# mcu_rev1.net
KiCad netlist of a schematic drawn in EAGLE
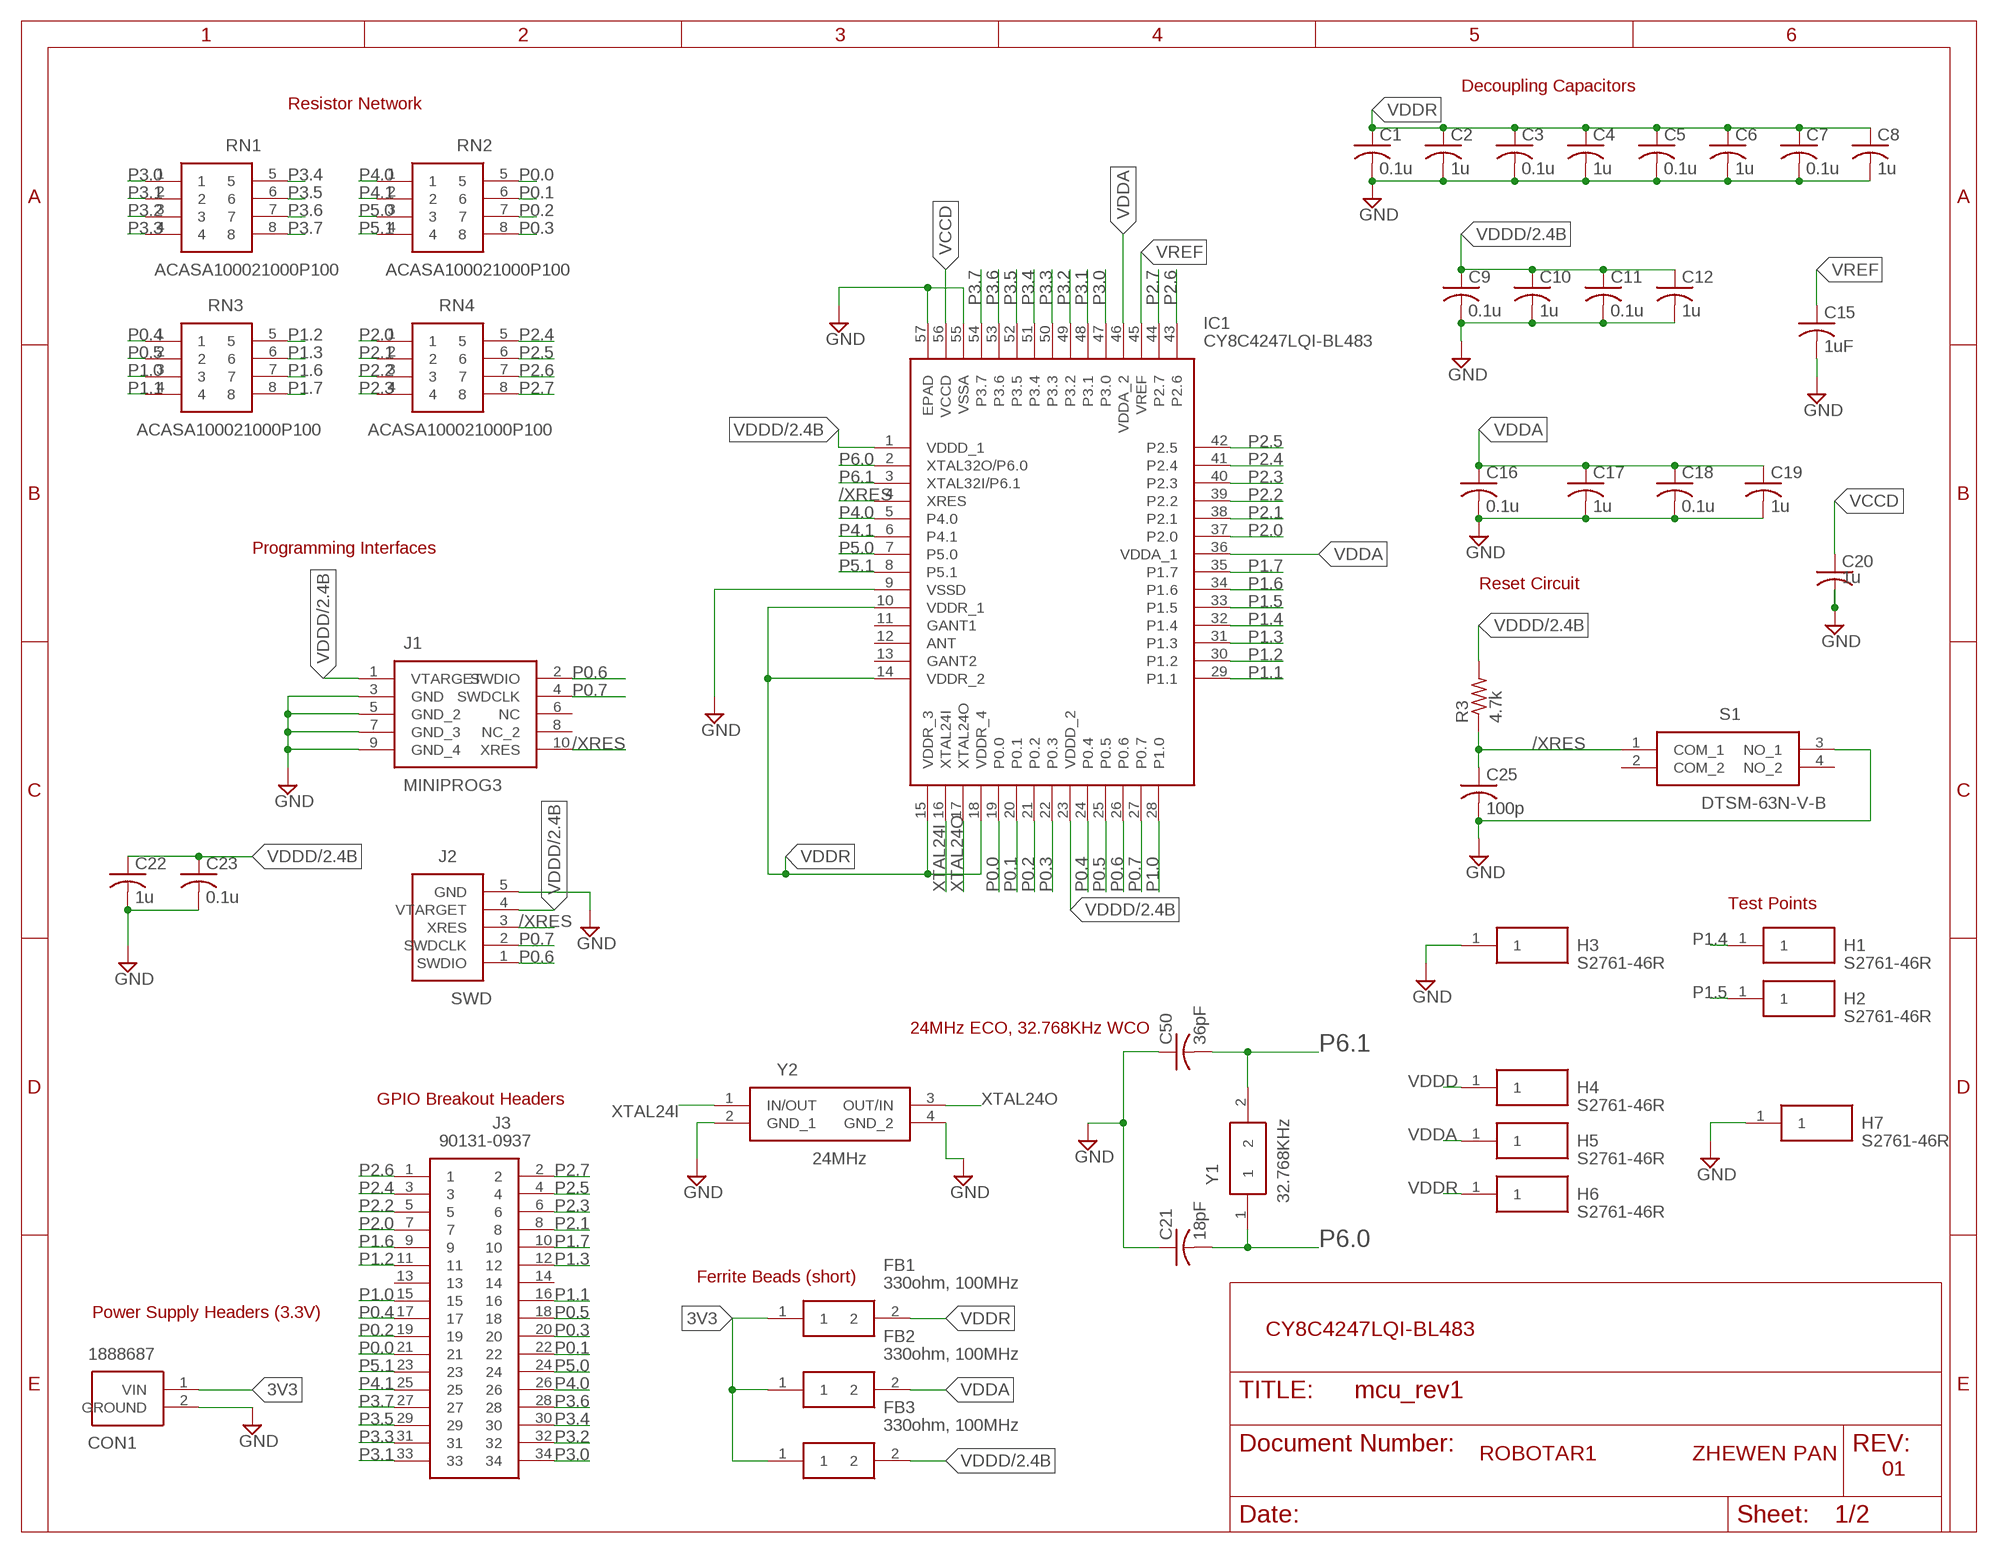
[diagram p0: schematic, sheet 1]
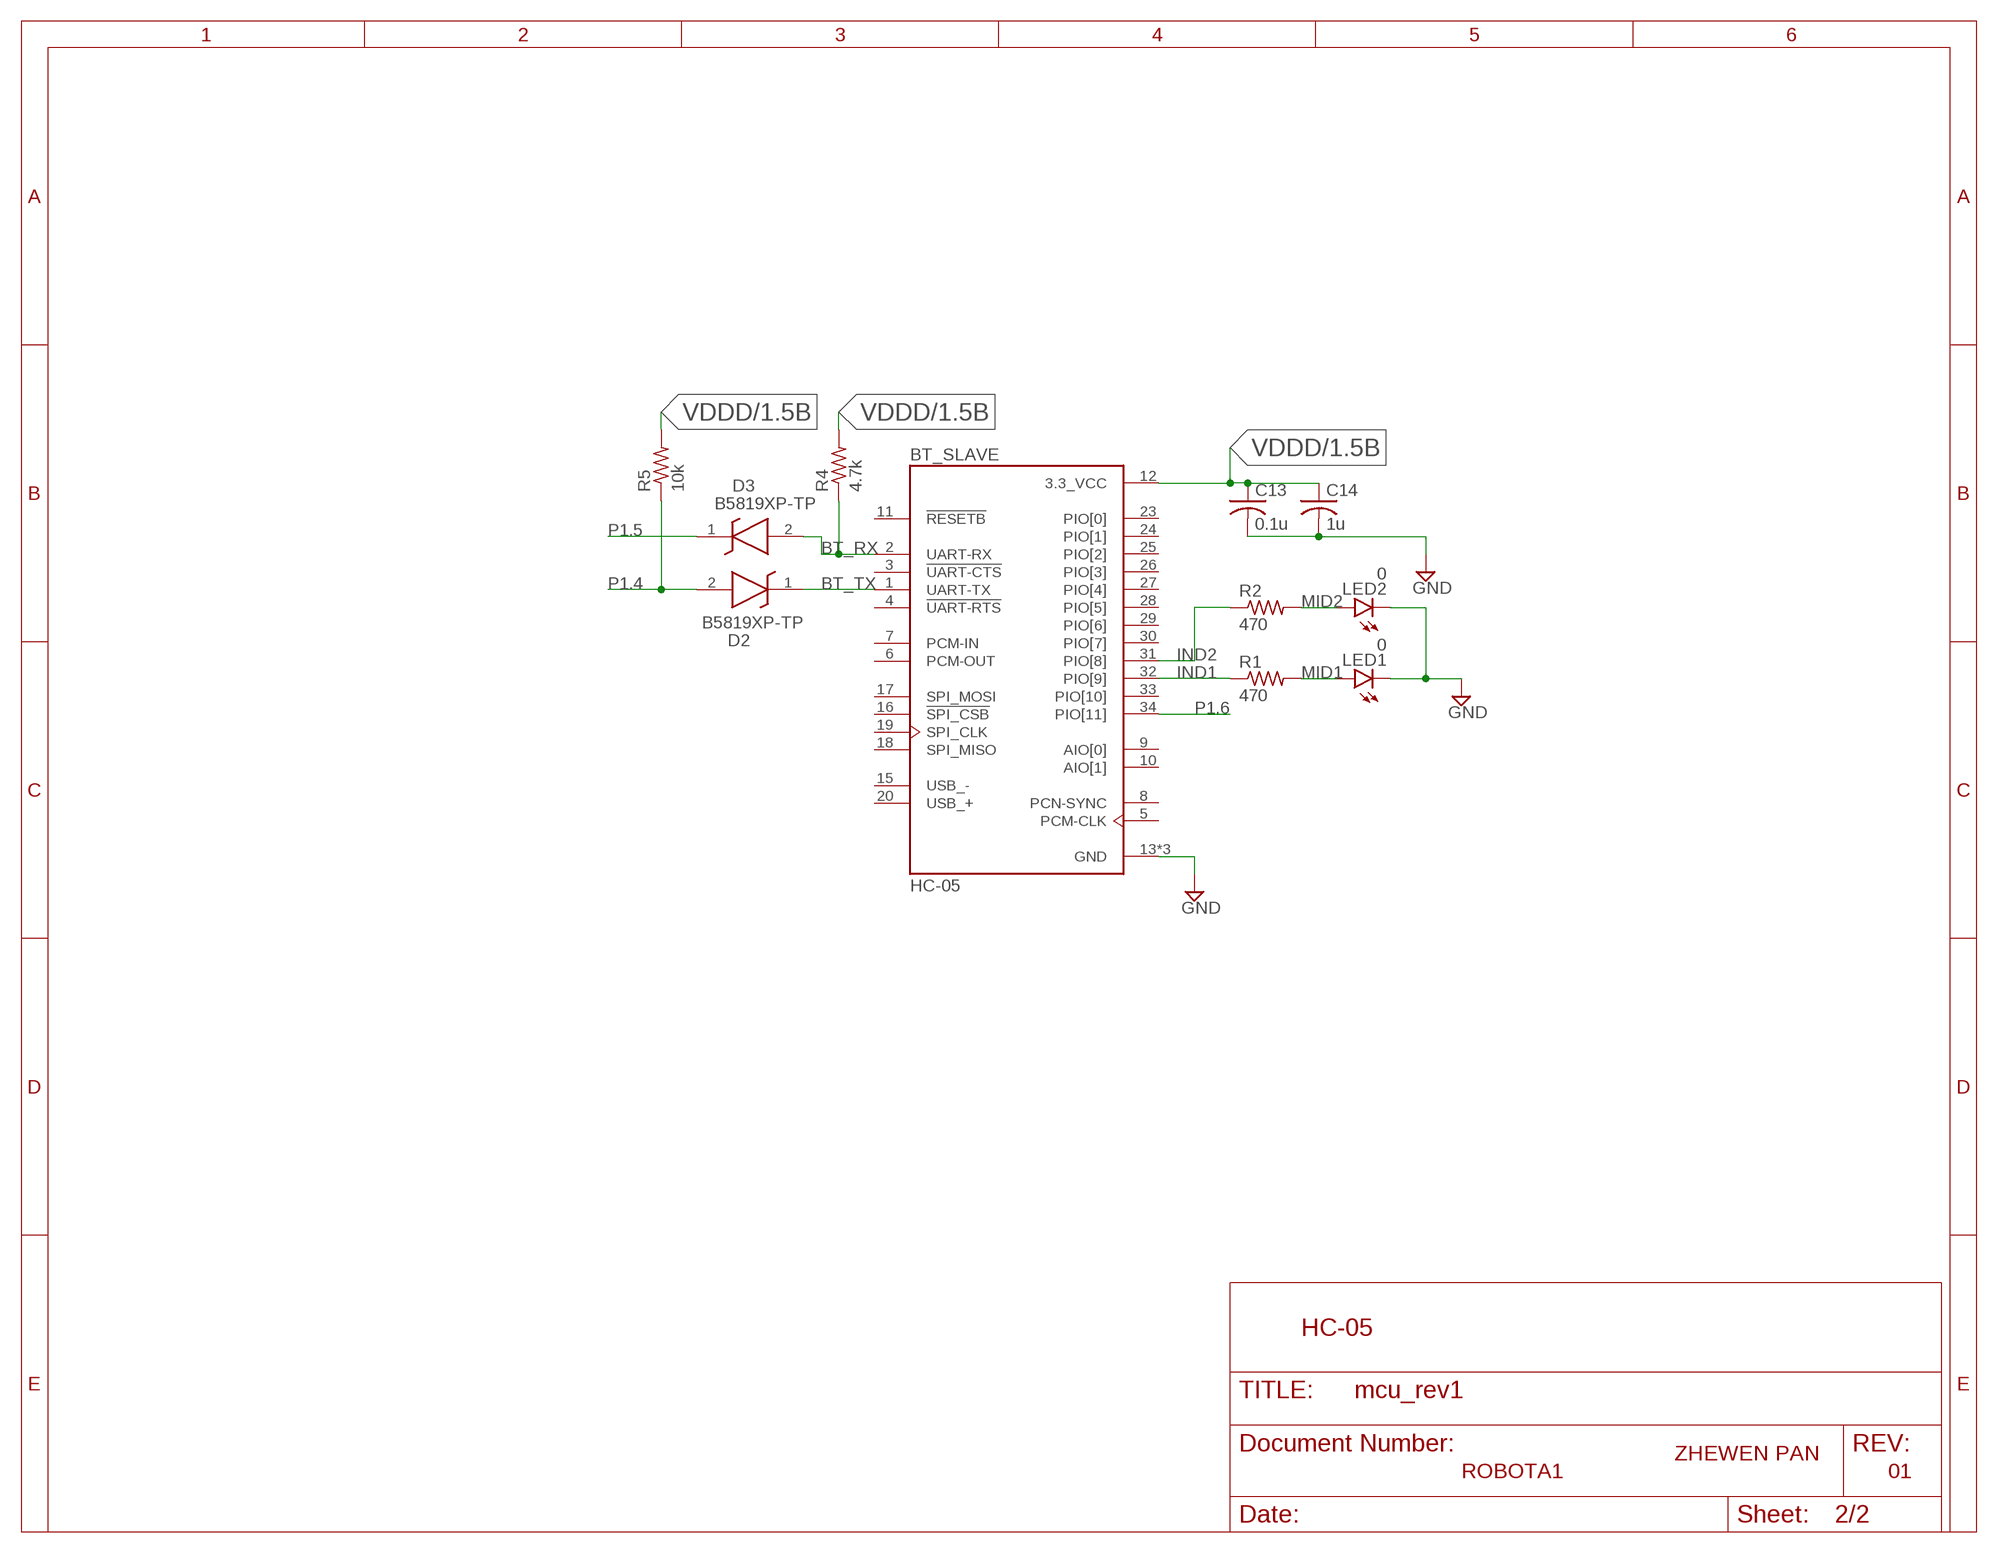
[diagram p1: schematic, sheet 2]

(export (version "E")
  (design (tool "Eeschema 10.0.6"))
  (components
    (comp (ref "BT_SLAVE")
      (value "HC-05")
      (footprint "eagle-import:XCVR_HC-05")
      (fields (field (name "MF") "Texas Instruments") (field (name "SPICEPREFIX") "X"))
      (libsource (lib "eagle-import") (part "HC-05"))
    )
    (comp (ref "C13")
      (value "0.1u")
      (footprint "eagle-import:C0805")
      (libsource (lib "eagle-import") (part "C-USC0805"))
    )
    (comp (ref "C14")
      (value "1u")
      (footprint "eagle-import:C0805")
      (libsource (lib "eagle-import") (part "C-USC0805"))
    )
    (comp (ref "D2")
      (value "B5819XP-TP")
      (footprint "eagle-import:B5819XPTP")
      (libsource (lib "eagle-import") (part "B5819XP-TP"))
    )
    (comp (ref "D3")
      (value "B5819XP-TP")
      (footprint "eagle-import:B5819XPTP")
      (libsource (lib "eagle-import") (part "B5819XP-TP"))
    )
    (comp (ref "LED1")
      (value "0")
      (footprint "eagle-import:SML0805")
      (libsource (lib "eagle-import") (part "LEDSML0805"))
    )
    (comp (ref "LED2")
      (value "0")
      (footprint "eagle-import:SML0805")
      (libsource (lib "eagle-import") (part "LEDSML0805"))
    )
    (comp (ref "R1")
      (value "470")
      (footprint "eagle-import:R0805")
      (libsource (lib "eagle-import") (part "R-US_R0805"))
    )
    (comp (ref "R2")
      (value "470")
      (footprint "eagle-import:R0805")
      (libsource (lib "eagle-import") (part "R-US_R0805"))
    )
    (comp (ref "R4")
      (value "4.7k")
      (footprint "eagle-import:R0805")
      (libsource (lib "eagle-import") (part "R-US_R0805"))
    )
    (comp (ref "R5")
      (value "10k")
      (footprint "eagle-import:R0805")
      (libsource (lib "eagle-import") (part "R-US_R0805"))
    )
    (comp (ref "C1")
      (value "0.1u")
      (footprint "eagle-import:C0805")
      (libsource (lib "eagle-import") (part "C-USC0805"))
    )
    (comp (ref "C2")
      (value "1u")
      (footprint "eagle-import:C0805")
      (libsource (lib "eagle-import") (part "C-USC0805"))
    )
    (comp (ref "C3")
      (value "0.1u")
      (footprint "eagle-import:C0805")
      (libsource (lib "eagle-import") (part "C-USC0805"))
    )
    (comp (ref "C4")
      (value "1u")
      (footprint "eagle-import:C0805")
      (libsource (lib "eagle-import") (part "C-USC0805"))
    )
    (comp (ref "C5")
      (value "0.1u")
      (footprint "eagle-import:C0805")
      (libsource (lib "eagle-import") (part "C-USC0805"))
    )
    (comp (ref "C6")
      (value "1u")
      (footprint "eagle-import:C0805")
      (libsource (lib "eagle-import") (part "C-USC0805"))
    )
    (comp (ref "C7")
      (value "0.1u")
      (footprint "eagle-import:C0805")
      (libsource (lib "eagle-import") (part "C-USC0805"))
    )
    (comp (ref "C8")
      (value "1u")
      (footprint "eagle-import:C0805")
      (libsource (lib "eagle-import") (part "C-USC0805"))
    )
    (comp (ref "C9")
      (value "0.1u")
      (footprint "eagle-import:C0805")
      (libsource (lib "eagle-import") (part "C-USC0805"))
    )
    (comp (ref "C10")
      (value "1u")
      (footprint "eagle-import:C0805")
      (libsource (lib "eagle-import") (part "C-USC0805"))
    )
    (comp (ref "C11")
      (value "0.1u")
      (footprint "eagle-import:C0805")
      (libsource (lib "eagle-import") (part "C-USC0805"))
    )
    (comp (ref "C12")
      (value "1u")
      (footprint "eagle-import:C0805")
      (libsource (lib "eagle-import") (part "C-USC0805"))
    )
    (comp (ref "C15")
      (value "1uF")
      (footprint "eagle-import:C0805")
      (libsource (lib "eagle-import") (part "C-USC0805"))
    )
    (comp (ref "C16")
      (value "0.1u")
      (footprint "eagle-import:C0805")
      (libsource (lib "eagle-import") (part "C-USC0805"))
    )
    (comp (ref "C17")
      (value "1u")
      (footprint "eagle-import:C0805")
      (libsource (lib "eagle-import") (part "C-USC0805"))
    )
    (comp (ref "C18")
      (value "0.1u")
      (footprint "eagle-import:C0805")
      (libsource (lib "eagle-import") (part "C-USC0805"))
    )
    (comp (ref "C19")
      (value "1u")
      (footprint "eagle-import:C0805")
      (libsource (lib "eagle-import") (part "C-USC0805"))
    )
    (comp (ref "C20")
      (value "1u")
      (footprint "eagle-import:C0805")
      (libsource (lib "eagle-import") (part "C-USC0805"))
    )
    (comp (ref "C21")
      (value "18pF")
      (footprint "eagle-import:C0805")
      (libsource (lib "eagle-import") (part "C-USC0805"))
    )
    (comp (ref "C22")
      (value "1u")
      (footprint "eagle-import:C0805")
      (libsource (lib "eagle-import") (part "C-USC0805"))
    )
    (comp (ref "C23")
      (value "0.1u")
      (footprint "eagle-import:C0805")
      (libsource (lib "eagle-import") (part "C-USC0805"))
    )
    (comp (ref "C25")
      (value "100p")
      (footprint "eagle-import:C0805")
      (libsource (lib "eagle-import") (part "C-USC0805"))
    )
    (comp (ref "C50")
      (value "36pF")
      (footprint "eagle-import:C0805")
      (libsource (lib "eagle-import") (part "C-USC0805"))
    )
    (comp (ref "CON1")
      (value "1888687")
      (footprint "eagle-import:SHDR2W90P0X508_1X2_1016X950X15")
      (fields (field (name "RS_PART_NUMBER") "8045095"))
      (libsource (lib "eagle-import") (part "1888687"))
    )
    (comp (ref "FB1")
      (value "330ohm, 100MHz")
      (footprint "eagle-import:BEADC2012X105N")
      (fields
        (field (name "MANUFACTURER_PART_NUMBER") "BLM21PG331SN1D")
        (field (name "RS_PART_NUMBER") "7241545P")
      )
      (libsource (lib "eagle-import") (part "BLM21PG331SN1D"))
    )
    (comp (ref "FB2")
      (value "330ohm, 100MHz")
      (footprint "eagle-import:BEADC2012X105N")
      (fields
        (field (name "MANUFACTURER_PART_NUMBER") "BLM21PG331SN1D")
        (field (name "RS_PART_NUMBER") "7241545P")
      )
      (libsource (lib "eagle-import") (part "BLM21PG331SN1D"))
    )
    (comp (ref "FB3")
      (value "330ohm, 100MHz")
      (footprint "eagle-import:BEADC2012X105N")
      (fields
        (field (name "MANUFACTURER_PART_NUMBER") "BLM21PG331SN1D")
        (field (name "RS_PART_NUMBER") "7241545P")
      )
      (libsource (lib "eagle-import") (part "BLM21PG331SN1D"))
    )
    (comp (ref "H1")
      (value "S2761-46R")
      (footprint "eagle-import:S276146R")
      (libsource (lib "eagle-import") (part "S2761-46R"))
    )
    (comp (ref "H2")
      (value "S2761-46R")
      (footprint "eagle-import:S276146R")
      (libsource (lib "eagle-import") (part "S2761-46R"))
    )
    (comp (ref "H3")
      (value "S2761-46R")
      (footprint "eagle-import:S276146R")
      (libsource (lib "eagle-import") (part "S2761-46R"))
    )
    (comp (ref "H4")
      (value "S2761-46R")
      (footprint "eagle-import:S276146R")
      (libsource (lib "eagle-import") (part "S2761-46R"))
    )
    (comp (ref "H5")
      (value "S2761-46R")
      (footprint "eagle-import:S276146R")
      (libsource (lib "eagle-import") (part "S2761-46R"))
    )
    (comp (ref "H6")
      (value "S2761-46R")
      (footprint "eagle-import:S276146R")
      (libsource (lib "eagle-import") (part "S2761-46R"))
    )
    (comp (ref "H7")
      (value "S2761-46R")
      (footprint "eagle-import:S276146R")
      (libsource (lib "eagle-import") (part "S2761-46R"))
    )
    (comp (ref "IC1")
      (value "CY8C4247LQI-BL483")
      (footprint "eagle-import:QFN40P700X700X60-57N")
      (fields (field (name "RS_PART_NUMBER") "1242964P"))
      (libsource (lib "eagle-import") (part "CY8C4247LQI-BL483"))
    )
    (comp (ref "J1")
      (value "MINIPROG3")
      (footprint "eagle-import:FTSH-105-01-L-DV-K")
      (fields
        (field (name "MANUFACTURER_PART_NUMBER") "FTSH-105-01-L-DV-K")
        (field (name "RS_PART_NUMBER") "1592332")
      )
      (libsource (lib "eagle-import") (part "FTSH-105-01-L-DV-K"))
    )
    (comp (ref "J2")
      (value "SWD")
      (footprint "eagle-import:HDRV5W64P0X254_1X5_1255X635X81")
      (fields
        (field (name "MANUFACTURER_PART_NUMBER") "22-23-2051")
        (field (name "RS_PART_NUMBER") "1888757")
      )
      (libsource (lib "eagle-import") (part "22-23-2051"))
    )
    (comp (ref "J3")
      (value "90131-0937")
      (footprint "eagle-import:HDRV34W90P254_2X17_4308X500X56")
      (fields (field (name "RS_PART_NUMBER") "6703569"))
      (libsource (lib "eagle-import") (part "90131-0937"))
    )
    (comp (ref "R3")
      (value "4.7k")
      (footprint "eagle-import:R0805")
      (libsource (lib "eagle-import") (part "R-US_R0805"))
    )
    (comp (ref "RN1")
      (value "ACASA100021000P100")
      (footprint "eagle-import:ACASA100021000P100")
      (fields (field (name "RS_PART_NUMBER") "6845742P"))
      (libsource (lib "eagle-import") (part "ACASA100021000P100"))
    )
    (comp (ref "RN2")
      (value "ACASA100021000P100")
      (footprint "eagle-import:ACASA100021000P100")
      (fields (field (name "RS_PART_NUMBER") "6845742P"))
      (libsource (lib "eagle-import") (part "ACASA100021000P100"))
    )
    (comp (ref "RN3")
      (value "ACASA100021000P100")
      (footprint "eagle-import:ACASA100021000P100")
      (fields (field (name "RS_PART_NUMBER") "6845742P"))
      (libsource (lib "eagle-import") (part "ACASA100021000P100"))
    )
    (comp (ref "RN4")
      (value "ACASA100021000P100")
      (footprint "eagle-import:ACASA100021000P100")
      (fields (field (name "RS_PART_NUMBER") "6845742P"))
      (libsource (lib "eagle-import") (part "ACASA100021000P100"))
    )
    (comp (ref "S1")
      (value "DTSM-63N-V-B")
      (footprint "eagle-import:DTSM63NVB")
      (libsource (lib "eagle-import") (part "DTSM-63N-V-B"))
    )
    (comp (ref "Y1")
      (value "32.768KHz")
      (footprint "eagle-import:ECX-31B")
      (fields (field (name "MANUFACTURER_PART_NUMBER") "ECS-.327-12.5-34B-TR"))
      (libsource (lib "eagle-import") (part "ECS-.327-12.5-34B-TR"))
    )
    (comp (ref "Y2")
      (value "24MHz")
      (footprint "eagle-import:ECS240836QAESTR")
      (fields (field (name "MANUFACTURER_PART_NUMBER") "ECS-240-8-36CKM-TR") (field (name "SPICEPREFIX") "E"))
      (libsource (lib "eagle-import") (part "ECS-240-8-36CKM-TR"))
    )
  )
  (nets
    (net (code "1") (name "3V3") (class "Default")
      (node (ref "CON1") (pin "1") (pinfunction "VIN_1") (pintype "bidirectional"))
      (node (ref "FB1") (pin "1") (pinfunction "1_1") (pintype "bidirectional"))
      (node (ref "FB2") (pin "1") (pinfunction "1_1") (pintype "bidirectional"))
      (node (ref "FB3") (pin "1") (pinfunction "1_1") (pintype "bidirectional"))
    )
    (net (code "2") (name "BT_RX") (class "Default")
      (node (ref "BT_SLAVE") (pin "2") (pinfunction "UART-RX_2") (pintype "input"))
      (node (ref "D3") (pin "2") (pinfunction "+_2") (pintype "bidirectional"))
      (node (ref "R4") (pin "1") (pinfunction "1_1") (pintype "passive"))
    )
    (net (code "3") (name "BT_TX") (class "Default")
      (node (ref "BT_SLAVE") (pin "1") (pinfunction "UART-TX_1") (pintype "output"))
      (node (ref "D2") (pin "1") (pinfunction "-_1") (pintype "bidirectional"))
    )
    (net (code "4") (name "GND") (class "Default")
      (node (ref "BT_SLAVE") (pin "13") (pinfunction "GND_13") (pintype "power_in"))
      (node (ref "BT_SLAVE") (pin "21") (pinfunction "GND_21") (pintype "power_in"))
      (node (ref "BT_SLAVE") (pin "22") (pinfunction "GND_22") (pintype "power_in"))
      (node (ref "C1") (pin "2") (pinfunction "2_2") (pintype "passive"))
      (node (ref "C10") (pin "2") (pinfunction "2_2") (pintype "passive"))
      (node (ref "C11") (pin "2") (pinfunction "2_2") (pintype "passive"))
      (node (ref "C12") (pin "2") (pinfunction "2_2") (pintype "passive"))
      (node (ref "C13") (pin "2") (pinfunction "2_2") (pintype "passive"))
      (node (ref "C14") (pin "2") (pinfunction "2_2") (pintype "passive"))
      (node (ref "C15") (pin "2") (pinfunction "2_2") (pintype "passive"))
      (node (ref "C16") (pin "2") (pinfunction "2_2") (pintype "passive"))
      (node (ref "C17") (pin "2") (pinfunction "2_2") (pintype "passive"))
      (node (ref "C18") (pin "2") (pinfunction "2_2") (pintype "passive"))
      (node (ref "C19") (pin "2") (pinfunction "2_2") (pintype "passive"))
      (node (ref "C2") (pin "2") (pinfunction "2_2") (pintype "passive"))
      (node (ref "C20") (pin "2") (pinfunction "2_2") (pintype "passive"))
      (node (ref "C21") (pin "1") (pinfunction "1_1") (pintype "passive"))
      (node (ref "C22") (pin "2") (pinfunction "2_2") (pintype "passive"))
      (node (ref "C23") (pin "2") (pinfunction "2_2") (pintype "passive"))
      (node (ref "C25") (pin "2") (pinfunction "2_2") (pintype "passive"))
      (node (ref "C3") (pin "2") (pinfunction "2_2") (pintype "passive"))
      (node (ref "C4") (pin "2") (pinfunction "2_2") (pintype "passive"))
      (node (ref "C5") (pin "2") (pinfunction "2_2") (pintype "passive"))
      (node (ref "C50") (pin "1") (pinfunction "1_1") (pintype "passive"))
      (node (ref "C6") (pin "2") (pinfunction "2_2") (pintype "passive"))
      (node (ref "C7") (pin "2") (pinfunction "2_2") (pintype "passive"))
      (node (ref "C8") (pin "2") (pinfunction "2_2") (pintype "passive"))
      (node (ref "C9") (pin "2") (pinfunction "2_2") (pintype "passive"))
      (node (ref "CON1") (pin "2") (pinfunction "GROUND_2") (pintype "bidirectional"))
      (node (ref "H3") (pin "1") (pinfunction "1_1") (pintype "bidirectional"))
      (node (ref "H7") (pin "1") (pinfunction "1_1") (pintype "bidirectional"))
      (node (ref "IC1") (pin "55") (pinfunction "VSSA_55") (pintype "bidirectional"))
      (node (ref "IC1") (pin "57") (pinfunction "EPAD_57") (pintype "bidirectional"))
      (node (ref "IC1") (pin "9") (pinfunction "VSSD_9") (pintype "bidirectional"))
      (node (ref "J1") (pin "3") (pinfunction "GND_3") (pintype "bidirectional"))
      (node (ref "J1") (pin "5") (pinfunction "GND_2_5") (pintype "bidirectional"))
      (node (ref "J1") (pin "7") (pinfunction "GND_3_7") (pintype "bidirectional"))
      (node (ref "J1") (pin "9") (pinfunction "GND_4_9") (pintype "bidirectional"))
      (node (ref "J2") (pin "5") (pinfunction "GND_5") (pintype "bidirectional"))
      (node (ref "LED1") (pin "C") (pinfunction "C_C") (pintype "passive"))
      (node (ref "LED2") (pin "C") (pinfunction "C_C") (pintype "passive"))
      (node (ref "S1") (pin "3") (pinfunction "NO_1_3") (pintype "bidirectional"))
      (node (ref "Y2") (pin "2") (pinfunction "GND_1_2") (pintype "bidirectional"))
      (node (ref "Y2") (pin "4") (pinfunction "GND_2_4") (pintype "bidirectional"))
    )
    (net (code "5") (name "IND1") (class "Default")
      (node (ref "BT_SLAVE") (pin "32") (pinfunction "PIO[9]_32") (pintype "bidirectional"))
      (node (ref "R1") (pin "1") (pinfunction "1_1") (pintype "passive"))
    )
    (net (code "6") (name "IND2") (class "Default")
      (node (ref "BT_SLAVE") (pin "31") (pinfunction "PIO[8]_31") (pintype "bidirectional"))
      (node (ref "R2") (pin "1") (pinfunction "1_1") (pintype "passive"))
    )
    (net (code "7") (name "MID1") (class "Default")
      (node (ref "LED1") (pin "A") (pinfunction "A_A") (pintype "passive"))
      (node (ref "R1") (pin "2") (pinfunction "2_2") (pintype "passive"))
    )
    (net (code "8") (name "MID2") (class "Default")
      (node (ref "LED2") (pin "A") (pinfunction "A_A") (pintype "passive"))
      (node (ref "R2") (pin "2") (pinfunction "2_2") (pintype "passive"))
    )
    (net (code "9") (name "P0.0") (class "Default")
      (node (ref "IC1") (pin "19") (pinfunction "P0.0_19") (pintype "bidirectional"))
      (node (ref "J3") (pin "21") (pinfunction "21_21") (pintype "bidirectional"))
      (node (ref "RN2") (pin "5") (pinfunction "5_5") (pintype "bidirectional"))
    )
    (net (code "10") (name "P0.1") (class "Default")
      (node (ref "IC1") (pin "20") (pinfunction "P0.1_20") (pintype "bidirectional"))
      (node (ref "J3") (pin "22") (pinfunction "22_22") (pintype "bidirectional"))
      (node (ref "RN2") (pin "6") (pinfunction "6_6") (pintype "bidirectional"))
    )
    (net (code "11") (name "P0.2") (class "Default")
      (node (ref "IC1") (pin "21") (pinfunction "P0.2_21") (pintype "bidirectional"))
      (node (ref "J3") (pin "19") (pinfunction "19_19") (pintype "bidirectional"))
      (node (ref "RN2") (pin "7") (pinfunction "7_7") (pintype "bidirectional"))
    )
    (net (code "12") (name "P0.3") (class "Default")
      (node (ref "IC1") (pin "22") (pinfunction "P0.3_22") (pintype "bidirectional"))
      (node (ref "J3") (pin "20") (pinfunction "20_20") (pintype "bidirectional"))
      (node (ref "RN2") (pin "8") (pinfunction "8_8") (pintype "bidirectional"))
    )
    (net (code "13") (name "P0.4") (class "Default")
      (node (ref "IC1") (pin "24") (pinfunction "P0.4_24") (pintype "bidirectional"))
      (node (ref "J3") (pin "17") (pinfunction "17_17") (pintype "bidirectional"))
      (node (ref "RN3") (pin "1") (pinfunction "1_1") (pintype "bidirectional"))
    )
    (net (code "14") (name "P0.5") (class "Default")
      (node (ref "IC1") (pin "25") (pinfunction "P0.5_25") (pintype "bidirectional"))
      (node (ref "J3") (pin "18") (pinfunction "18_18") (pintype "bidirectional"))
      (node (ref "RN3") (pin "2") (pinfunction "2_2") (pintype "bidirectional"))
    )
    (net (code "15") (name "P0.6") (class "Default")
      (node (ref "IC1") (pin "26") (pinfunction "P0.6_26") (pintype "bidirectional"))
      (node (ref "J1") (pin "2") (pinfunction "SWDIO_2") (pintype "bidirectional"))
      (node (ref "J2") (pin "1") (pinfunction "SWDIO_1") (pintype "bidirectional"))
    )
    (net (code "16") (name "P0.7") (class "Default")
      (node (ref "IC1") (pin "27") (pinfunction "P0.7_27") (pintype "bidirectional"))
      (node (ref "J1") (pin "4") (pinfunction "SWDCLK_4") (pintype "bidirectional"))
      (node (ref "J2") (pin "2") (pinfunction "SWDCLK_2") (pintype "bidirectional"))
    )
    (net (code "17") (name "P1.0") (class "Default")
      (node (ref "IC1") (pin "28") (pinfunction "P1.0_28") (pintype "bidirectional"))
      (node (ref "J3") (pin "15") (pinfunction "15_15") (pintype "bidirectional"))
      (node (ref "RN3") (pin "3") (pinfunction "3_3") (pintype "bidirectional"))
    )
    (net (code "18") (name "P1.1") (class "Default")
      (node (ref "IC1") (pin "29") (pinfunction "P1.1_29") (pintype "bidirectional"))
      (node (ref "J3") (pin "16") (pinfunction "16_16") (pintype "bidirectional"))
      (node (ref "RN3") (pin "4") (pinfunction "4_4") (pintype "bidirectional"))
    )
    (net (code "19") (name "P1.2") (class "Default")
      (node (ref "IC1") (pin "30") (pinfunction "P1.2_30") (pintype "bidirectional"))
      (node (ref "J3") (pin "11") (pinfunction "11_11") (pintype "bidirectional"))
      (node (ref "RN3") (pin "5") (pinfunction "5_5") (pintype "bidirectional"))
    )
    (net (code "20") (name "P1.3") (class "Default")
      (node (ref "IC1") (pin "31") (pinfunction "P1.3_31") (pintype "bidirectional"))
      (node (ref "J3") (pin "12") (pinfunction "12_12") (pintype "bidirectional"))
      (node (ref "RN3") (pin "6") (pinfunction "6_6") (pintype "bidirectional"))
    )
    (net (code "21") (name "P1.4") (class "Default")
      (node (ref "D2") (pin "2") (pinfunction "+_2") (pintype "bidirectional"))
      (node (ref "H1") (pin "1") (pinfunction "1_1") (pintype "bidirectional"))
      (node (ref "IC1") (pin "32") (pinfunction "P1.4_32") (pintype "bidirectional"))
      (node (ref "R5") (pin "1") (pinfunction "1_1") (pintype "passive"))
    )
    (net (code "22") (name "P1.5") (class "Default")
      (node (ref "D3") (pin "1") (pinfunction "-_1") (pintype "bidirectional"))
      (node (ref "H2") (pin "1") (pinfunction "1_1") (pintype "bidirectional"))
      (node (ref "IC1") (pin "33") (pinfunction "P1.5_33") (pintype "bidirectional"))
    )
    (net (code "23") (name "P1.6") (class "Default")
      (node (ref "BT_SLAVE") (pin "34") (pinfunction "PIO[11]_34") (pintype "bidirectional"))
      (node (ref "IC1") (pin "34") (pinfunction "P1.6_34") (pintype "bidirectional"))
      (node (ref "J3") (pin "9") (pinfunction "9_9") (pintype "bidirectional"))
      (node (ref "RN3") (pin "7") (pinfunction "7_7") (pintype "bidirectional"))
    )
    (net (code "24") (name "P1.7") (class "Default")
      (node (ref "IC1") (pin "35") (pinfunction "P1.7_35") (pintype "bidirectional"))
      (node (ref "J3") (pin "10") (pinfunction "10_10") (pintype "bidirectional"))
      (node (ref "RN3") (pin "8") (pinfunction "8_8") (pintype "bidirectional"))
    )
    (net (code "25") (name "P2.0") (class "Default")
      (node (ref "IC1") (pin "37") (pinfunction "P2.0_37") (pintype "bidirectional"))
      (node (ref "J3") (pin "7") (pinfunction "7_7") (pintype "bidirectional"))
      (node (ref "RN4") (pin "1") (pinfunction "1_1") (pintype "bidirectional"))
    )
    (net (code "26") (name "P2.1") (class "Default")
      (node (ref "IC1") (pin "38") (pinfunction "P2.1_38") (pintype "bidirectional"))
      (node (ref "J3") (pin "8") (pinfunction "8_8") (pintype "bidirectional"))
      (node (ref "RN4") (pin "2") (pinfunction "2_2") (pintype "bidirectional"))
    )
    (net (code "27") (name "P2.2") (class "Default")
      (node (ref "IC1") (pin "39") (pinfunction "P2.2_39") (pintype "bidirectional"))
      (node (ref "J3") (pin "5") (pinfunction "5_5") (pintype "bidirectional"))
      (node (ref "RN4") (pin "3") (pinfunction "3_3") (pintype "bidirectional"))
    )
    (net (code "28") (name "P2.3") (class "Default")
      (node (ref "IC1") (pin "40") (pinfunction "P2.3_40") (pintype "bidirectional"))
      (node (ref "J3") (pin "6") (pinfunction "6_6") (pintype "bidirectional"))
      (node (ref "RN4") (pin "4") (pinfunction "4_4") (pintype "bidirectional"))
    )
    (net (code "29") (name "P2.4") (class "Default")
      (node (ref "IC1") (pin "41") (pinfunction "P2.4_41") (pintype "bidirectional"))
      (node (ref "J3") (pin "3") (pinfunction "3_3") (pintype "bidirectional"))
      (node (ref "RN4") (pin "5") (pinfunction "5_5") (pintype "bidirectional"))
    )
    (net (code "30") (name "P2.5") (class "Default")
      (node (ref "IC1") (pin "42") (pinfunction "P2.5_42") (pintype "bidirectional"))
      (node (ref "J3") (pin "4") (pinfunction "4_4") (pintype "bidirectional"))
      (node (ref "RN4") (pin "6") (pinfunction "6_6") (pintype "bidirectional"))
    )
    (net (code "31") (name "P2.6") (class "Default")
      (node (ref "IC1") (pin "43") (pinfunction "P2.6_43") (pintype "bidirectional"))
      (node (ref "J3") (pin "1") (pinfunction "1_1") (pintype "bidirectional"))
      (node (ref "RN4") (pin "7") (pinfunction "7_7") (pintype "bidirectional"))
    )
    (net (code "32") (name "P2.7") (class "Default")
      (node (ref "IC1") (pin "44") (pinfunction "P2.7_44") (pintype "bidirectional"))
      (node (ref "J3") (pin "2") (pinfunction "2_2") (pintype "bidirectional"))
      (node (ref "RN4") (pin "8") (pinfunction "8_8") (pintype "bidirectional"))
    )
    (net (code "33") (name "P3.0") (class "Default")
      (node (ref "IC1") (pin "47") (pinfunction "P3.0_47") (pintype "bidirectional"))
      (node (ref "J3") (pin "34") (pinfunction "34_34") (pintype "bidirectional"))
      (node (ref "RN1") (pin "1") (pinfunction "1_1") (pintype "bidirectional"))
    )
    (net (code "34") (name "P3.1") (class "Default")
      (node (ref "IC1") (pin "48") (pinfunction "P3.1_48") (pintype "bidirectional"))
      (node (ref "J3") (pin "33") (pinfunction "33_33") (pintype "bidirectional"))
      (node (ref "RN1") (pin "2") (pinfunction "2_2") (pintype "bidirectional"))
    )
    (net (code "35") (name "P3.2") (class "Default")
      (node (ref "IC1") (pin "49") (pinfunction "P3.2_49") (pintype "bidirectional"))
      (node (ref "J3") (pin "32") (pinfunction "32_32") (pintype "bidirectional"))
      (node (ref "RN1") (pin "3") (pinfunction "3_3") (pintype "bidirectional"))
    )
    (net (code "36") (name "P3.3") (class "Default")
      (node (ref "IC1") (pin "50") (pinfunction "P3.3_50") (pintype "bidirectional"))
      (node (ref "J3") (pin "31") (pinfunction "31_31") (pintype "bidirectional"))
      (node (ref "RN1") (pin "4") (pinfunction "4_4") (pintype "bidirectional"))
    )
    (net (code "37") (name "P3.4") (class "Default")
      (node (ref "IC1") (pin "51") (pinfunction "P3.4_51") (pintype "bidirectional"))
      (node (ref "J3") (pin "30") (pinfunction "30_30") (pintype "bidirectional"))
      (node (ref "RN1") (pin "5") (pinfunction "5_5") (pintype "bidirectional"))
    )
    (net (code "38") (name "P3.5") (class "Default")
      (node (ref "IC1") (pin "52") (pinfunction "P3.5_52") (pintype "bidirectional"))
      (node (ref "J3") (pin "29") (pinfunction "29_29") (pintype "bidirectional"))
      (node (ref "RN1") (pin "6") (pinfunction "6_6") (pintype "bidirectional"))
    )
    (net (code "39") (name "P3.6") (class "Default")
      (node (ref "IC1") (pin "53") (pinfunction "P3.6_53") (pintype "bidirectional"))
      (node (ref "J3") (pin "28") (pinfunction "28_28") (pintype "bidirectional"))
      (node (ref "RN1") (pin "7") (pinfunction "7_7") (pintype "bidirectional"))
    )
    (net (code "40") (name "P3.7") (class "Default")
      (node (ref "IC1") (pin "54") (pinfunction "P3.7_54") (pintype "bidirectional"))
      (node (ref "J3") (pin "27") (pinfunction "27_27") (pintype "bidirectional"))
      (node (ref "RN1") (pin "8") (pinfunction "8_8") (pintype "bidirectional"))
    )
    (net (code "41") (name "P4.0") (class "Default")
      (node (ref "IC1") (pin "5") (pinfunction "P4.0_5") (pintype "bidirectional"))
      (node (ref "J3") (pin "26") (pinfunction "26_26") (pintype "bidirectional"))
      (node (ref "RN2") (pin "1") (pinfunction "1_1") (pintype "bidirectional"))
    )
    (net (code "42") (name "P4.1") (class "Default")
      (node (ref "IC1") (pin "6") (pinfunction "P4.1_6") (pintype "bidirectional"))
      (node (ref "J3") (pin "25") (pinfunction "25_25") (pintype "bidirectional"))
      (node (ref "RN2") (pin "2") (pinfunction "2_2") (pintype "bidirectional"))
    )
    (net (code "43") (name "P5.0") (class "Default")
      (node (ref "IC1") (pin "7") (pinfunction "P5.0_7") (pintype "bidirectional"))
      (node (ref "J3") (pin "24") (pinfunction "24_24") (pintype "bidirectional"))
      (node (ref "RN2") (pin "3") (pinfunction "3_3") (pintype "bidirectional"))
    )
    (net (code "44") (name "P5.1") (class "Default")
      (node (ref "IC1") (pin "8") (pinfunction "P5.1_8") (pintype "bidirectional"))
      (node (ref "J3") (pin "23") (pinfunction "23_23") (pintype "bidirectional"))
      (node (ref "RN2") (pin "4") (pinfunction "4_4") (pintype "bidirectional"))
    )
    (net (code "45") (name "P6.0") (class "Default")
      (node (ref "C21") (pin "2") (pinfunction "2_2") (pintype "passive"))
      (node (ref "IC1") (pin "2") (pinfunction "XTAL32O/P6.0_2") (pintype "bidirectional"))
      (node (ref "Y1") (pin "1") (pinfunction "1_1") (pintype "bidirectional"))
    )
    (net (code "46") (name "P6.1") (class "Default")
      (node (ref "C50") (pin "2") (pinfunction "2_2") (pintype "passive"))
      (node (ref "IC1") (pin "3") (pinfunction "XTAL32I/P6.1_3") (pintype "bidirectional"))
      (node (ref "Y1") (pin "2") (pinfunction "2_2") (pintype "bidirectional"))
    )
    (net (code "47") (name "VCCD") (class "Default")
      (node (ref "C20") (pin "1") (pinfunction "1_1") (pintype "passive"))
      (node (ref "IC1") (pin "56") (pinfunction "VCCD_56") (pintype "bidirectional"))
    )
    (net (code "48") (name "VDDA") (class "Default")
      (node (ref "C16") (pin "1") (pinfunction "1_1") (pintype "passive"))
      (node (ref "C17") (pin "1") (pinfunction "1_1") (pintype "passive"))
      (node (ref "C18") (pin "1") (pinfunction "1_1") (pintype "passive"))
      (node (ref "C19") (pin "1") (pinfunction "1_1") (pintype "passive"))
      (node (ref "FB2") (pin "2") (pinfunction "2_2") (pintype "bidirectional"))
      (node (ref "H5") (pin "1") (pinfunction "1_1") (pintype "bidirectional"))
      (node (ref "IC1") (pin "36") (pinfunction "VDDA_1_36") (pintype "bidirectional"))
      (node (ref "IC1") (pin "46") (pinfunction "VDDA_2_46") (pintype "bidirectional"))
    )
    (net (code "49") (name "VDDD") (class "Default")
      (node (ref "BT_SLAVE") (pin "12") (pinfunction "3.3_VCC_12") (pintype "power_in"))
      (node (ref "C10") (pin "1") (pinfunction "1_1") (pintype "passive"))
      (node (ref "C11") (pin "1") (pinfunction "1_1") (pintype "passive"))
      (node (ref "C12") (pin "1") (pinfunction "1_1") (pintype "passive"))
      (node (ref "C13") (pin "1") (pinfunction "1_1") (pintype "passive"))
      (node (ref "C14") (pin "1") (pinfunction "1_1") (pintype "passive"))
      (node (ref "C22") (pin "1") (pinfunction "1_1") (pintype "passive"))
      (node (ref "C23") (pin "1") (pinfunction "1_1") (pintype "passive"))
      (node (ref "C9") (pin "1") (pinfunction "1_1") (pintype "passive"))
      (node (ref "FB3") (pin "2") (pinfunction "2_2") (pintype "bidirectional"))
      (node (ref "H4") (pin "1") (pinfunction "1_1") (pintype "bidirectional"))
      (node (ref "IC1") (pin "1") (pinfunction "VDDD_1_1") (pintype "bidirectional"))
      (node (ref "IC1") (pin "23") (pinfunction "VDDD_2_23") (pintype "bidirectional"))
      (node (ref "J1") (pin "1") (pinfunction "VTARGET_1") (pintype "bidirectional"))
      (node (ref "J2") (pin "4") (pinfunction "VTARGET_4") (pintype "bidirectional"))
      (node (ref "R3") (pin "2") (pinfunction "2_2") (pintype "passive"))
      (node (ref "R4") (pin "2") (pinfunction "2_2") (pintype "passive"))
      (node (ref "R5") (pin "2") (pinfunction "2_2") (pintype "passive"))
    )
    (net (code "50") (name "VDDR") (class "Default")
      (node (ref "C1") (pin "1") (pinfunction "1_1") (pintype "passive"))
      (node (ref "C2") (pin "1") (pinfunction "1_1") (pintype "passive"))
      (node (ref "C3") (pin "1") (pinfunction "1_1") (pintype "passive"))
      (node (ref "C4") (pin "1") (pinfunction "1_1") (pintype "passive"))
      (node (ref "C5") (pin "1") (pinfunction "1_1") (pintype "passive"))
      (node (ref "C6") (pin "1") (pinfunction "1_1") (pintype "passive"))
      (node (ref "C7") (pin "1") (pinfunction "1_1") (pintype "passive"))
      (node (ref "C8") (pin "1") (pinfunction "1_1") (pintype "passive"))
      (node (ref "FB1") (pin "2") (pinfunction "2_2") (pintype "bidirectional"))
      (node (ref "H6") (pin "1") (pinfunction "1_1") (pintype "bidirectional"))
      (node (ref "IC1") (pin "10") (pinfunction "VDDR_1_10") (pintype "bidirectional"))
      (node (ref "IC1") (pin "14") (pinfunction "VDDR_2_14") (pintype "bidirectional"))
      (node (ref "IC1") (pin "15") (pinfunction "VDDR_3_15") (pintype "bidirectional"))
      (node (ref "IC1") (pin "18") (pinfunction "VDDR_4_18") (pintype "bidirectional"))
    )
    (net (code "51") (name "VREF") (class "Default")
      (node (ref "C15") (pin "1") (pinfunction "1_1") (pintype "passive"))
      (node (ref "IC1") (pin "45") (pinfunction "VREF_45") (pintype "bidirectional"))
    )
    (net (code "52") (name "XTAL24I") (class "Default")
      (node (ref "IC1") (pin "16") (pinfunction "XTAL24I_16") (pintype "bidirectional"))
      (node (ref "Y2") (pin "1") (pinfunction "IN/OUT_1") (pintype "bidirectional"))
    )
    (net (code "53") (name "XTAL24O") (class "Default")
      (node (ref "IC1") (pin "17") (pinfunction "XTAL24O_17") (pintype "bidirectional"))
      (node (ref "Y2") (pin "3") (pinfunction "OUT/IN_3") (pintype "bidirectional"))
    )
    (net (code "54") (name "unconnected-(BT_SLAVE-AIO[0]-Pad9)") (class "Default")
      (node (ref "BT_SLAVE") (pin "9") (pinfunction "AIO[0]_9") (pintype "bidirectional"))
    )
    (net (code "55") (name "unconnected-(BT_SLAVE-AIO[1]-Pad10)") (class "Default")
      (node (ref "BT_SLAVE") (pin "10") (pinfunction "AIO[1]_10") (pintype "bidirectional"))
    )
    (net (code "56") (name "unconnected-(BT_SLAVE-PCM-CLK-Pad5)") (class "Default")
      (node (ref "BT_SLAVE") (pin "5") (pinfunction "PCM-CLK_5") (pintype "bidirectional"))
    )
    (net (code "57") (name "unconnected-(BT_SLAVE-PCM-IN-Pad7)") (class "Default")
      (node (ref "BT_SLAVE") (pin "7") (pinfunction "PCM-IN_7") (pintype "input"))
    )
    (net (code "58") (name "unconnected-(BT_SLAVE-PCM-OUT-Pad6)") (class "Default")
      (node (ref "BT_SLAVE") (pin "6") (pinfunction "PCM-OUT_6") (pintype "output"))
    )
    (net (code "59") (name "unconnected-(BT_SLAVE-PCN-SYNC-Pad8)") (class "Default")
      (node (ref "BT_SLAVE") (pin "8") (pinfunction "PCN-SYNC_8") (pintype "bidirectional"))
    )
    (net (code "60") (name "unconnected-(BT_SLAVE-PIO[0]-Pad23)") (class "Default")
      (node (ref "BT_SLAVE") (pin "23") (pinfunction "PIO[0]_23") (pintype "bidirectional"))
    )
    (net (code "61") (name "unconnected-(BT_SLAVE-PIO[1]-Pad24)") (class "Default")
      (node (ref "BT_SLAVE") (pin "24") (pinfunction "PIO[1]_24") (pintype "bidirectional"))
    )
    (net (code "62") (name "unconnected-(BT_SLAVE-PIO[2]-Pad25)") (class "Default")
      (node (ref "BT_SLAVE") (pin "25") (pinfunction "PIO[2]_25") (pintype "bidirectional"))
    )
    (net (code "63") (name "unconnected-(BT_SLAVE-PIO[3]-Pad26)") (class "Default")
      (node (ref "BT_SLAVE") (pin "26") (pinfunction "PIO[3]_26") (pintype "bidirectional"))
    )
    (net (code "64") (name "unconnected-(BT_SLAVE-PIO[4]-Pad27)") (class "Default")
      (node (ref "BT_SLAVE") (pin "27") (pinfunction "PIO[4]_27") (pintype "bidirectional"))
    )
    (net (code "65") (name "unconnected-(BT_SLAVE-PIO[5]-Pad28)") (class "Default")
      (node (ref "BT_SLAVE") (pin "28") (pinfunction "PIO[5]_28") (pintype "bidirectional"))
    )
    (net (code "66") (name "unconnected-(BT_SLAVE-PIO[6]-Pad29)") (class "Default")
      (node (ref "BT_SLAVE") (pin "29") (pinfunction "PIO[6]_29") (pintype "bidirectional"))
    )
    (net (code "67") (name "unconnected-(BT_SLAVE-PIO[7]-Pad30)") (class "Default")
      (node (ref "BT_SLAVE") (pin "30") (pinfunction "PIO[7]_30") (pintype "bidirectional"))
    )
    (net (code "68") (name "unconnected-(BT_SLAVE-PIO[10]-Pad33)") (class "Default")
      (node (ref "BT_SLAVE") (pin "33") (pinfunction "PIO[10]_33") (pintype "bidirectional"))
    )
    (net (code "69") (name "unconnected-(BT_SLAVE-SPI_CLK-Pad19)") (class "Default")
      (node (ref "BT_SLAVE") (pin "19") (pinfunction "SPI_CLK_19") (pintype "input"))
    )
    (net (code "70") (name "unconnected-(BT_SLAVE-SPI_MISO-Pad18)") (class "Default")
      (node (ref "BT_SLAVE") (pin "18") (pinfunction "SPI_MISO_18") (pintype "output"))
    )
    (net (code "71") (name "unconnected-(BT_SLAVE-SPI_MOSI-Pad17)") (class "Default")
      (node (ref "BT_SLAVE") (pin "17") (pinfunction "SPI_MOSI_17") (pintype "input"))
    )
    (net (code "72") (name "unconnected-(BT_SLAVE-USB_+-Pad20)") (class "Default")
      (node (ref "BT_SLAVE") (pin "20") (pinfunction "USB_+_20") (pintype "bidirectional"))
    )
    (net (code "73") (name "unconnected-(BT_SLAVE-USB_--Pad15)") (class "Default")
      (node (ref "BT_SLAVE") (pin "15") (pinfunction "USB_-_15") (pintype "bidirectional"))
    )
    (net (code "74") (name "unconnected-(BT_SLAVE-~{RESETB}-Pad11)") (class "Default")
      (node (ref "BT_SLAVE") (pin "11") (pinfunction "~{RESETB}_11") (pintype "input"))
    )
    (net (code "75") (name "unconnected-(BT_SLAVE-~{SPI_CSB}-Pad16)") (class "Default")
      (node (ref "BT_SLAVE") (pin "16") (pinfunction "~{SPI_CSB}_16") (pintype "input"))
    )
    (net (code "76") (name "unconnected-(BT_SLAVE-~{UART-CTS}-Pad3)") (class "Default")
      (node (ref "BT_SLAVE") (pin "3") (pinfunction "~{UART-CTS}_3") (pintype "input"))
    )
    (net (code "77") (name "unconnected-(BT_SLAVE-~{UART-RTS}-Pad4)") (class "Default")
      (node (ref "BT_SLAVE") (pin "4") (pinfunction "~{UART-RTS}_4") (pintype "output"))
    )
    (net (code "78") (name "unconnected-(IC1-ANT-Pad12)") (class "Default")
      (node (ref "IC1") (pin "12") (pinfunction "ANT_12") (pintype "bidirectional"))
    )
    (net (code "79") (name "unconnected-(IC1-GANT1-Pad11)") (class "Default")
      (node (ref "IC1") (pin "11") (pinfunction "GANT1_11") (pintype "bidirectional"))
    )
    (net (code "80") (name "unconnected-(IC1-GANT2-Pad13)") (class "Default")
      (node (ref "IC1") (pin "13") (pinfunction "GANT2_13") (pintype "bidirectional"))
    )
    (net (code "81") (name "unconnected-(J1-NC-Pad6)") (class "Default")
      (node (ref "J1") (pin "6") (pinfunction "NC_6") (pintype "bidirectional"))
    )
    (net (code "82") (name "unconnected-(J1-NC_2-Pad8)") (class "Default")
      (node (ref "J1") (pin "8") (pinfunction "NC_2_8") (pintype "bidirectional"))
    )
    (net (code "83") (name "unconnected-(J3-Pad13)") (class "Default")
      (node (ref "J3") (pin "13") (pinfunction "13_13") (pintype "bidirectional"))
    )
    (net (code "84") (name "unconnected-(J3-Pad14)") (class "Default")
      (node (ref "J3") (pin "14") (pinfunction "14_14") (pintype "bidirectional"))
    )
    (net (code "85") (name "unconnected-(S1-COM_2-Pad2)") (class "Default")
      (node (ref "S1") (pin "2") (pinfunction "COM_2_2") (pintype "bidirectional"))
    )
    (net (code "86") (name "unconnected-(S1-NO_2-Pad4)") (class "Default")
      (node (ref "S1") (pin "4") (pinfunction "NO_2_4") (pintype "bidirectional"))
    )
    (net (code "87") (name "{slash}XRES") (class "Default")
      (node (ref "C25") (pin "1") (pinfunction "1_1") (pintype "passive"))
      (node (ref "IC1") (pin "4") (pinfunction "XRES_4") (pintype "bidirectional"))
      (node (ref "J1") (pin "10") (pinfunction "XRES_10") (pintype "bidirectional"))
      (node (ref "J2") (pin "3") (pinfunction "XRES_3") (pintype "bidirectional"))
      (node (ref "R3") (pin "1") (pinfunction "1_1") (pintype "passive"))
      (node (ref "S1") (pin "1") (pinfunction "COM_1_1") (pintype "bidirectional"))
    )
  )
)
